# mian.net
KiCad netlist of a schematic drawn in Altium Designer
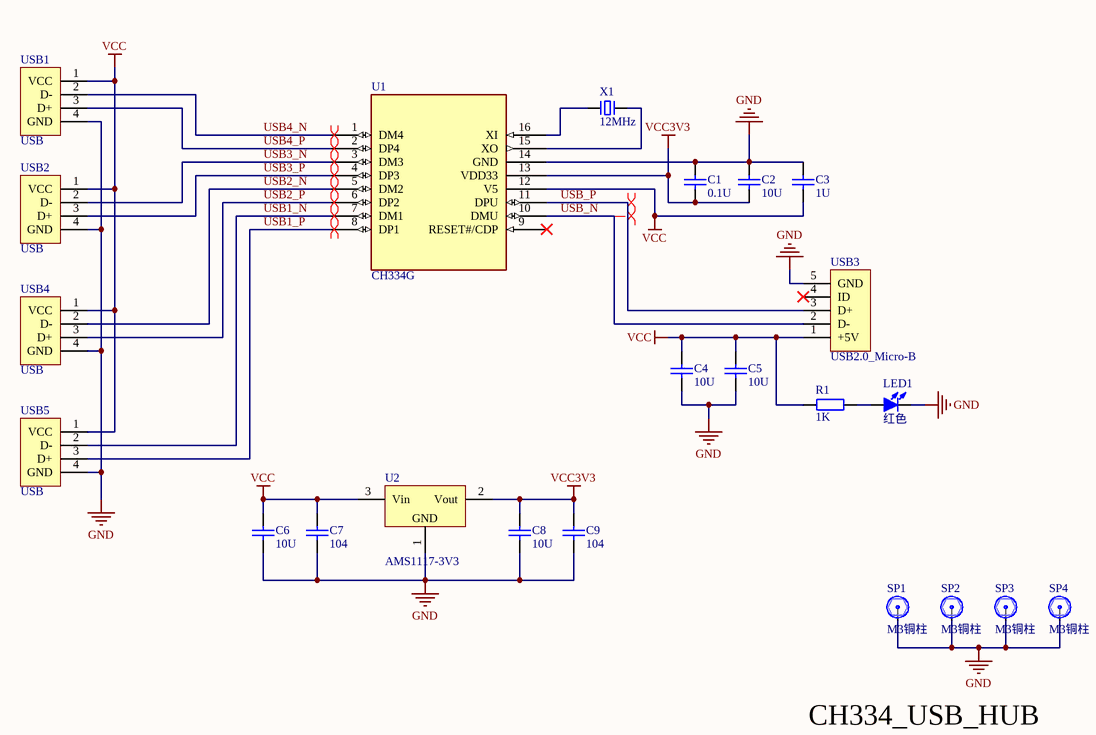
[diagram p0: mian.SchDoc]

(export (version "E")
  (design (tool "Eeschema 10.0.6"))
  (components
    (comp (ref "C1")
      (value "0.1U")
      (footprint "C0805_L")
      (description "贴片电容/MLCC电容")
      (libsource (lib "0.1 - 电阻-电容-电感-晶振-晶体-磁珠-电位器-法拉电容-馈通电容") (part "C"))
    )
    (comp (ref "C2")
      (value "10U")
      (footprint "C0805_L")
      (description "贴片电容/MLCC电容")
      (libsource (lib "0.1 - 电阻-电容-电感-晶振-晶体-磁珠-电位器-法拉电容-馈通电容") (part "C"))
    )
    (comp (ref "C3")
      (value "1U")
      (footprint "C0805_L")
      (description "贴片电容/MLCC电容")
      (libsource (lib "0.1 - 电阻-电容-电感-晶振-晶体-磁珠-电位器-法拉电容-馈通电容") (part "C"))
    )
    (comp (ref "C4")
      (value "10U")
      (footprint "C0805_L")
      (description "贴片电容/MLCC电容")
      (libsource (lib "0.1 - 电阻-电容-电感-晶振-晶体-磁珠-电位器-法拉电容-馈通电容") (part "C"))
    )
    (comp (ref "C5")
      (value "10U")
      (footprint "C0805_L")
      (description "贴片电容/MLCC电容")
      (libsource (lib "0.1 - 电阻-电容-电感-晶振-晶体-磁珠-电位器-法拉电容-馈通电容") (part "C"))
    )
    (comp (ref "C6")
      (value "10U")
      (footprint "C0805_L")
      (description "贴片电容/MLCC电容")
      (libsource (lib "0.1 - 电阻-电容-电感-晶振-晶体-磁珠-电位器-法拉电容-馈通电容") (part "C"))
    )
    (comp (ref "C7")
      (value "104")
      (footprint "C0805_L")
      (description "贴片电容/MLCC电容")
      (libsource (lib "0.1 - 电阻-电容-电感-晶振-晶体-磁珠-电位器-法拉电容-馈通电容") (part "C"))
    )
    (comp (ref "C8")
      (value "10U")
      (footprint "C0805_L")
      (description "贴片电容/MLCC电容")
      (libsource (lib "0.1 - 电阻-电容-电感-晶振-晶体-磁珠-电位器-法拉电容-馈通电容") (part "C"))
    )
    (comp (ref "C9")
      (value "104")
      (footprint "C0805_L")
      (description "贴片电容/MLCC电容")
      (libsource (lib "0.1 - 电阻-电容-电感-晶振-晶体-磁珠-电位器-法拉电容-馈通电容") (part "C"))
    )
    (comp (ref "LED1")
      (value "红色")
      (footprint "LED0805_R")
      (description "贴片LED")
      (libsource (lib "0.3 - LED发光二极管-IR二极管_接收管-光耦") (part "LED-SMD"))
    )
    (comp (ref "R1")
      (value "1K")
      (footprint "R0805_L")
      (description "贴片电阻")
      (libsource (lib "0.1 - 电阻-电容-电感-晶振-晶体-磁珠-电位器-法拉电容-馈通电容") (part "R"))
    )
    (comp (ref "SP1")
      (value "M3铜柱")
      (footprint "M3x4_N")
      (description "铜柱")
      (libsource (lib "0.5 - 按键_开关_蜂鸣器_保险丝_电池_测试点_Mark点_铜柱") (part "铜柱大焊盘"))
    )
    (comp (ref "SP2")
      (value "M3铜柱")
      (footprint "M3x4_N")
      (description "铜柱")
      (libsource (lib "0.5 - 按键_开关_蜂鸣器_保险丝_电池_测试点_Mark点_铜柱") (part "铜柱大焊盘"))
    )
    (comp (ref "SP3")
      (value "M3铜柱")
      (footprint "M3x4_N")
      (description "铜柱")
      (libsource (lib "0.5 - 按键_开关_蜂鸣器_保险丝_电池_测试点_Mark点_铜柱") (part "铜柱大焊盘"))
    )
    (comp (ref "SP4")
      (value "M3铜柱")
      (footprint "M3x4_N")
      (description "铜柱")
      (libsource (lib "0.5 - 按键_开关_蜂鸣器_保险丝_电池_测试点_Mark点_铜柱") (part "铜柱大焊盘"))
    )
    (comp (ref "U1")
      (value "CH334G")
      (footprint "SOP16")
      (description "4 ports High-Speed USB STT Hub")
      (libsource (lib "CHXXX") (part "CH334G"))
    )
    (comp (ref "U2")
      (value "AMS1117-3V3")
      (footprint "SOT223_M")
      (description "三端稳压芯片")
      (libsource (lib "0.7 - 电源类芯片") (part "AMS1117_SOT89"))
    )
    (comp (ref "USB1")
      (value "USB")
      (footprint "USB2.0_Type-A_DIP_F_1")
      (description "USB2.0_Type-A母座")
      (libsource (lib "0.6 - 电源_RJ45以太网_音频_SD-TF_SIM_ USB Type-C_HDMI插座") (part "USB2.0_Type-A_F"))
    )
    (comp (ref "USB2")
      (value "USB")
      (footprint "USB2.0_Type-A_DIP_F_1")
      (description "USB2.0_Type-A母座")
      (libsource (lib "0.6 - 电源_RJ45以太网_音频_SD-TF_SIM_ USB Type-C_HDMI插座") (part "USB2.0_Type-A_F"))
    )
    (comp (ref "USB3")
      (value "USB2.0_Micro-B")
      (footprint "USB2.0_MICRO-B_1")
      (description "USB2.0_Micro-B母座")
      (libsource (lib "0.6 - 电源_RJ45以太网_音频_SD-TF_SIM_ USB Type-C_HDMI插座") (part "USB2.0_Micro-B"))
    )
    (comp (ref "USB4")
      (value "USB")
      (footprint "USB2.0_Type-A_DIP_F_1")
      (description "USB2.0_Type-A母座")
      (libsource (lib "0.6 - 电源_RJ45以太网_音频_SD-TF_SIM_ USB Type-C_HDMI插座") (part "USB2.0_Type-A_F"))
    )
    (comp (ref "USB5")
      (value "USB")
      (footprint "USB2.0_Type-A_DIP_F_1")
      (description "USB2.0_Type-A母座")
      (libsource (lib "0.6 - 电源_RJ45以太网_音频_SD-TF_SIM_ USB Type-C_HDMI插座") (part "USB2.0_Type-A_F"))
    )
    (comp (ref "X1")
      (value "12MHz")
      (footprint "HC-49S")
      (description "2脚无源晶振(谐振器）")
      (libsource (lib "0.1 - 电阻-电容-电感-晶振-晶体-磁珠-电位器-法拉电容-馈通电容") (part "XTAL-2P"))
    )
  )
  (nets
    (net (code "1") (name "/USB1_N") (class "Default")
      (node (ref "U1") (pin "7") (pinfunction "DM1_7") (pintype "bidirectional"))
      (node (ref "USB5") (pin "2") (pinfunction "D-_2") (pintype "passive"))
    )
    (net (code "2") (name "/USB1_P") (class "Default")
      (node (ref "U1") (pin "8") (pinfunction "DP1_8") (pintype "bidirectional"))
      (node (ref "USB5") (pin "3") (pinfunction "D+_3") (pintype "passive"))
    )
    (net (code "3") (name "/USB2_N") (class "Default")
      (node (ref "U1") (pin "5") (pinfunction "DM2_5") (pintype "bidirectional"))
      (node (ref "USB4") (pin "2") (pinfunction "D-_2") (pintype "passive"))
    )
    (net (code "4") (name "/USB2_P") (class "Default")
      (node (ref "U1") (pin "6") (pinfunction "DP2_6") (pintype "bidirectional"))
      (node (ref "USB4") (pin "3") (pinfunction "D+_3") (pintype "passive"))
    )
    (net (code "5") (name "/USB3_N") (class "Default")
      (node (ref "U1") (pin "3") (pinfunction "DM3_3") (pintype "bidirectional"))
      (node (ref "USB2") (pin "2") (pinfunction "D-_2") (pintype "passive"))
    )
    (net (code "6") (name "/USB3_P") (class "Default")
      (node (ref "U1") (pin "4") (pinfunction "DP3_4") (pintype "bidirectional"))
      (node (ref "USB2") (pin "3") (pinfunction "D+_3") (pintype "passive"))
    )
    (net (code "7") (name "/USB4_N") (class "Default")
      (node (ref "U1") (pin "1") (pinfunction "DM4_1") (pintype "bidirectional"))
      (node (ref "USB1") (pin "2") (pinfunction "D-_2") (pintype "passive"))
    )
    (net (code "8") (name "/USB4_P") (class "Default")
      (node (ref "U1") (pin "2") (pinfunction "DP4_2") (pintype "bidirectional"))
      (node (ref "USB1") (pin "3") (pinfunction "D+_3") (pintype "passive"))
    )
    (net (code "9") (name "/USB_N") (class "Default")
      (node (ref "U1") (pin "10") (pinfunction "DMU_10") (pintype "bidirectional"))
      (node (ref "USB3") (pin "2") (pinfunction "D-_2") (pintype "passive"))
    )
    (net (code "10") (name "/USB_P") (class "Default")
      (node (ref "U1") (pin "11") (pinfunction "DPU_11") (pintype "bidirectional"))
      (node (ref "USB3") (pin "3") (pinfunction "D+_3") (pintype "passive"))
    )
    (net (code "11") (name "GND") (class "Default")
      (node (ref "C1") (pin "2") (pinfunction "2_2") (pintype "passive"))
      (node (ref "C2") (pin "2") (pinfunction "2_2") (pintype "passive"))
      (node (ref "C3") (pin "2") (pinfunction "2_2") (pintype "passive"))
      (node (ref "C4") (pin "1") (pinfunction "1_1") (pintype "passive"))
      (node (ref "C5") (pin "1") (pinfunction "1_1") (pintype "passive"))
      (node (ref "C6") (pin "1") (pinfunction "1_1") (pintype "passive"))
      (node (ref "C7") (pin "1") (pinfunction "1_1") (pintype "passive"))
      (node (ref "C8") (pin "1") (pinfunction "1_1") (pintype "passive"))
      (node (ref "C9") (pin "1") (pinfunction "1_1") (pintype "passive"))
      (node (ref "LED1") (pin "2") (pinfunction "K_2") (pintype "passive"))
      (node (ref "SP1") (pin "1") (pinfunction "1_1") (pintype "passive"))
      (node (ref "SP2") (pin "1") (pinfunction "1_1") (pintype "passive"))
      (node (ref "SP3") (pin "1") (pinfunction "1_1") (pintype "passive"))
      (node (ref "SP4") (pin "1") (pinfunction "1_1") (pintype "passive"))
      (node (ref "U1") (pin "14") (pinfunction "GND_14") (pintype "power_in"))
      (node (ref "U2") (pin "1") (pinfunction "GND_1") (pintype "passive"))
      (node (ref "USB1") (pin "4") (pinfunction "GND_4") (pintype "passive"))
      (node (ref "USB2") (pin "4") (pinfunction "GND_4") (pintype "passive"))
      (node (ref "USB3") (pin "5") (pinfunction "GND_5") (pintype "passive"))
      (node (ref "USB4") (pin "4") (pinfunction "GND_4") (pintype "passive"))
      (node (ref "USB5") (pin "4") (pinfunction "GND_4") (pintype "passive"))
    )
    (net (code "12") (name "Net-(LED1-A)") (class "Default")
      (node (ref "LED1") (pin "1") (pinfunction "A_1") (pintype "passive"))
      (node (ref "R1") (pin "2") (pinfunction "2_2") (pintype "passive"))
    )
    (net (code "13") (name "Net-(U1-XI)") (class "Default")
      (node (ref "U1") (pin "16") (pinfunction "XI_16") (pintype "input"))
      (node (ref "X1") (pin "1") (pinfunction "1_1") (pintype "passive"))
    )
    (net (code "14") (name "Net-(U1-XO)") (class "Default")
      (node (ref "U1") (pin "15") (pinfunction "XO_15") (pintype "output"))
      (node (ref "X1") (pin "2") (pinfunction "2_2") (pintype "passive"))
    )
    (net (code "15") (name "VCC") (class "Default")
      (node (ref "C3") (pin "1") (pinfunction "1_1") (pintype "passive"))
      (node (ref "C4") (pin "2") (pinfunction "2_2") (pintype "passive"))
      (node (ref "C5") (pin "2") (pinfunction "2_2") (pintype "passive"))
      (node (ref "C6") (pin "2") (pinfunction "2_2") (pintype "passive"))
      (node (ref "C7") (pin "2") (pinfunction "2_2") (pintype "passive"))
      (node (ref "R1") (pin "1") (pinfunction "1_1") (pintype "passive"))
      (node (ref "U1") (pin "12") (pinfunction "V5_12") (pintype "power_in"))
      (node (ref "U2") (pin "3") (pinfunction "Vin_3") (pintype "passive"))
      (node (ref "USB1") (pin "1") (pinfunction "VCC_1") (pintype "passive"))
      (node (ref "USB2") (pin "1") (pinfunction "VCC_1") (pintype "passive"))
      (node (ref "USB3") (pin "1") (pinfunction "+5V_1") (pintype "passive"))
      (node (ref "USB4") (pin "1") (pinfunction "VCC_1") (pintype "passive"))
      (node (ref "USB5") (pin "1") (pinfunction "VCC_1") (pintype "passive"))
    )
    (net (code "16") (name "VCC3V3") (class "Default")
      (node (ref "C1") (pin "1") (pinfunction "1_1") (pintype "passive"))
      (node (ref "C2") (pin "1") (pinfunction "1_1") (pintype "passive"))
      (node (ref "C8") (pin "2") (pinfunction "2_2") (pintype "passive"))
      (node (ref "C9") (pin "2") (pinfunction "2_2") (pintype "passive"))
      (node (ref "U1") (pin "13") (pinfunction "VDD33_13") (pintype "power_in"))
      (node (ref "U2") (pin "2") (pinfunction "Vout_2") (pintype "passive"))
    )
    (net (code "17") (name "unconnected-(U1-RESET#{slash}CDP-Pad9)") (class "Default")
      (node (ref "U1") (pin "9") (pinfunction "RESET#/CDP_9") (pintype "input+no_connect"))
    )
    (net (code "18") (name "unconnected-(USB3-ID-Pad4)") (class "Default")
      (node (ref "USB3") (pin "4") (pinfunction "ID_4") (pintype "passive+no_connect"))
    )
  )
)
